# Interconnect_board_v2p0.net
KiCad netlist of a schematic drawn in EAGLE
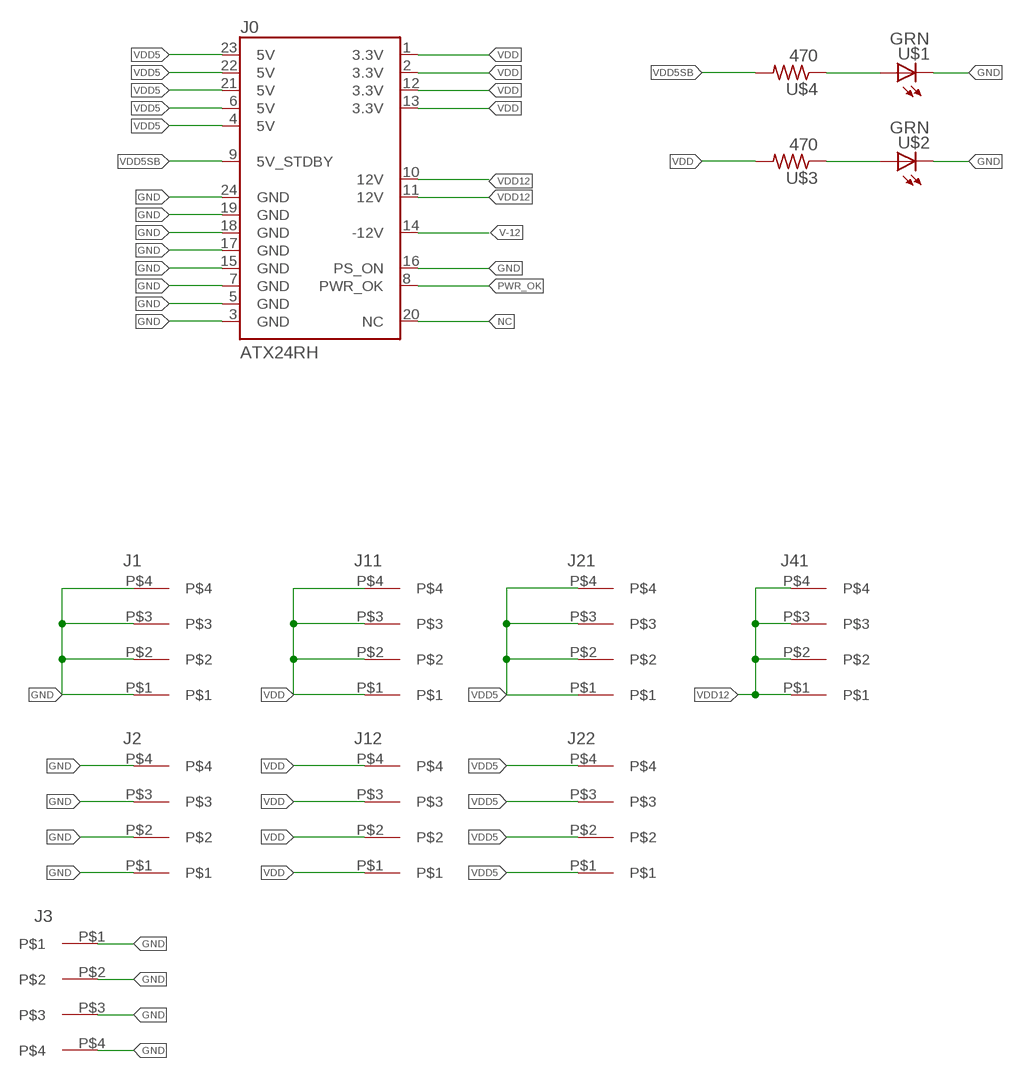
[diagram p0: schematic, sheet 1]

(export (version "E")
  (design (tool "Eeschema 10.0.6"))
  (components
    (comp (ref "J0")
      (value "ATX24RH")
      (footprint "eagle-import:ATX24_RIGHT_ANGLE")
      (libsource (lib "eagle-import") (part "ATX24RH"))
    )
    (comp (ref "J1")
      (value "3.81MM_1_X_4_RT_ANGLE_PLUG_HEADER")
      (footprint "eagle-import:1X4_3.81MM_PITCH")
      (libsource (lib "eagle-import") (part "3.81MM_1_X_4_RT_ANGLE_PLUG_HEADER"))
    )
    (comp (ref "J2")
      (value "3.81MM_1_X_4_RT_ANGLE_PLUG_HEADER")
      (footprint "eagle-import:1X4_3.81MM_PITCH")
      (libsource (lib "eagle-import") (part "3.81MM_1_X_4_RT_ANGLE_PLUG_HEADER"))
    )
    (comp (ref "J3")
      (value "3.81MM_1_X_4_RT_ANGLE_PLUG_HEADER")
      (footprint "eagle-import:1X4_3.81MM_PITCH")
      (libsource (lib "eagle-import") (part "3.81MM_1_X_4_RT_ANGLE_PLUG_HEADER"))
    )
    (comp (ref "J11")
      (value "3.81MM_1_X_4_RT_ANGLE_PLUG_HEADER")
      (footprint "eagle-import:1X4_3.81MM_PITCH")
      (libsource (lib "eagle-import") (part "3.81MM_1_X_4_RT_ANGLE_PLUG_HEADER"))
    )
    (comp (ref "J12")
      (value "3.81MM_1_X_4_RT_ANGLE_PLUG_HEADER")
      (footprint "eagle-import:1X4_3.81MM_PITCH")
      (libsource (lib "eagle-import") (part "3.81MM_1_X_4_RT_ANGLE_PLUG_HEADER"))
    )
    (comp (ref "J21")
      (value "3.81MM_1_X_4_RT_ANGLE_PLUG_HEADER")
      (footprint "eagle-import:1X4_3.81MM_PITCH")
      (libsource (lib "eagle-import") (part "3.81MM_1_X_4_RT_ANGLE_PLUG_HEADER"))
    )
    (comp (ref "J22")
      (value "3.81MM_1_X_4_RT_ANGLE_PLUG_HEADER")
      (footprint "eagle-import:1X4_3.81MM_PITCH")
      (libsource (lib "eagle-import") (part "3.81MM_1_X_4_RT_ANGLE_PLUG_HEADER"))
    )
    (comp (ref "J41")
      (value "3.81MM_1_X_4_RT_ANGLE_PLUG_HEADER")
      (footprint "eagle-import:1X4_3.81MM_PITCH")
      (libsource (lib "eagle-import") (part "3.81MM_1_X_4_RT_ANGLE_PLUG_HEADER"))
    )
    (comp (ref "U$1")
      (value "LED_0805_GREEN")
      (footprint "eagle-import:LED_0805_GREEN")
      (libsource (lib "eagle-import") (part "LED_0805_GREEN"))
    )
    (comp (ref "U$2")
      (value "LED_0805_GREEN")
      (footprint "eagle-import:LED_0805_GREEN")
      (libsource (lib "eagle-import") (part "LED_0805_GREEN"))
    )
    (comp (ref "U$3")
      (value "R_0805_470")
      (footprint "eagle-import:R_0805_470")
      (libsource (lib "eagle-import") (part "R_0805_470"))
    )
    (comp (ref "U$4")
      (value "R_0805_470")
      (footprint "eagle-import:R_0805_470")
      (libsource (lib "eagle-import") (part "R_0805_470"))
    )
  )
  (nets
    (net (code "1") (name "GND") (class "Default")
      (node (ref "J0") (pin "15") (pinfunction "GND_15") (pintype "bidirectional"))
      (node (ref "J0") (pin "16") (pinfunction "PS_ON_16") (pintype "bidirectional"))
      (node (ref "J0") (pin "17") (pinfunction "GND_17") (pintype "bidirectional"))
      (node (ref "J0") (pin "18") (pinfunction "GND_18") (pintype "bidirectional"))
      (node (ref "J0") (pin "19") (pinfunction "GND_19") (pintype "bidirectional"))
      (node (ref "J0") (pin "24") (pinfunction "GND_24") (pintype "bidirectional"))
      (node (ref "J0") (pin "3") (pinfunction "GND_3") (pintype "bidirectional"))
      (node (ref "J0") (pin "5") (pinfunction "GND_5") (pintype "bidirectional"))
      (node (ref "J0") (pin "7") (pinfunction "GND_7") (pintype "bidirectional"))
      (node (ref "J1") (pin "P$1") (pinfunction "P$1_P$1") (pintype "bidirectional"))
      (node (ref "J1") (pin "P$2") (pinfunction "P$2_P$2") (pintype "bidirectional"))
      (node (ref "J1") (pin "P$3") (pinfunction "P$3_P$3") (pintype "bidirectional"))
      (node (ref "J1") (pin "P$4") (pinfunction "P$4_P$4") (pintype "bidirectional"))
      (node (ref "J2") (pin "P$1") (pinfunction "P$1_P$1") (pintype "bidirectional"))
      (node (ref "J2") (pin "P$2") (pinfunction "P$2_P$2") (pintype "bidirectional"))
      (node (ref "J2") (pin "P$3") (pinfunction "P$3_P$3") (pintype "bidirectional"))
      (node (ref "J2") (pin "P$4") (pinfunction "P$4_P$4") (pintype "bidirectional"))
      (node (ref "J3") (pin "P$1") (pinfunction "P$1_P$1") (pintype "bidirectional"))
      (node (ref "J3") (pin "P$2") (pinfunction "P$2_P$2") (pintype "bidirectional"))
      (node (ref "J3") (pin "P$3") (pinfunction "P$3_P$3") (pintype "bidirectional"))
      (node (ref "J3") (pin "P$4") (pinfunction "P$4_P$4") (pintype "bidirectional"))
      (node (ref "U$1") (pin "C") (pinfunction "C_C") (pintype "passive"))
      (node (ref "U$2") (pin "C") (pinfunction "C_C") (pintype "passive"))
    )
    (net (code "2") (name "NC") (class "Default")
      (node (ref "J0") (pin "20") (pinfunction "NC_20") (pintype "bidirectional"))
    )
    (net (code "3") (name "Net-(U$1-PadA)") (class "Default")
      (node (ref "U$1") (pin "A") (pinfunction "A_A") (pintype "passive"))
      (node (ref "U$4") (pin "1") (pinfunction "1_1") (pintype "passive"))
    )
    (net (code "4") (name "Net-(U$2-PadA)") (class "Default")
      (node (ref "U$2") (pin "A") (pinfunction "A_A") (pintype "passive"))
      (node (ref "U$3") (pin "1") (pinfunction "1_1") (pintype "passive"))
    )
    (net (code "5") (name "PWR_OK") (class "Default")
      (node (ref "J0") (pin "8") (pinfunction "PWR_OK_8") (pintype "bidirectional"))
    )
    (net (code "6") (name "V-12") (class "Default")
      (node (ref "J0") (pin "14") (pinfunction "-12V_14") (pintype "bidirectional"))
    )
    (net (code "7") (name "VDD") (class "Default")
      (node (ref "J0") (pin "1") (pinfunction "3.3V_1") (pintype "bidirectional"))
      (node (ref "J0") (pin "12") (pinfunction "3.3V_12") (pintype "bidirectional"))
      (node (ref "J0") (pin "13") (pinfunction "3.3V_13") (pintype "bidirectional"))
      (node (ref "J0") (pin "2") (pinfunction "3.3V_2") (pintype "bidirectional"))
      (node (ref "J11") (pin "P$1") (pinfunction "P$1_P$1") (pintype "bidirectional"))
      (node (ref "J11") (pin "P$2") (pinfunction "P$2_P$2") (pintype "bidirectional"))
      (node (ref "J11") (pin "P$3") (pinfunction "P$3_P$3") (pintype "bidirectional"))
      (node (ref "J11") (pin "P$4") (pinfunction "P$4_P$4") (pintype "bidirectional"))
      (node (ref "J12") (pin "P$1") (pinfunction "P$1_P$1") (pintype "bidirectional"))
      (node (ref "J12") (pin "P$2") (pinfunction "P$2_P$2") (pintype "bidirectional"))
      (node (ref "J12") (pin "P$3") (pinfunction "P$3_P$3") (pintype "bidirectional"))
      (node (ref "J12") (pin "P$4") (pinfunction "P$4_P$4") (pintype "bidirectional"))
      (node (ref "U$3") (pin "2") (pinfunction "2_2") (pintype "passive"))
    )
    (net (code "8") (name "VDD5") (class "Default")
      (node (ref "J0") (pin "21") (pinfunction "5V_21") (pintype "bidirectional"))
      (node (ref "J0") (pin "22") (pinfunction "5V_22") (pintype "bidirectional"))
      (node (ref "J0") (pin "23") (pinfunction "5V_23") (pintype "bidirectional"))
      (node (ref "J0") (pin "4") (pinfunction "5V_4") (pintype "bidirectional"))
      (node (ref "J0") (pin "6") (pinfunction "5V_6") (pintype "bidirectional"))
      (node (ref "J21") (pin "P$1") (pinfunction "P$1_P$1") (pintype "bidirectional"))
      (node (ref "J21") (pin "P$2") (pinfunction "P$2_P$2") (pintype "bidirectional"))
      (node (ref "J21") (pin "P$3") (pinfunction "P$3_P$3") (pintype "bidirectional"))
      (node (ref "J21") (pin "P$4") (pinfunction "P$4_P$4") (pintype "bidirectional"))
      (node (ref "J22") (pin "P$1") (pinfunction "P$1_P$1") (pintype "bidirectional"))
      (node (ref "J22") (pin "P$2") (pinfunction "P$2_P$2") (pintype "bidirectional"))
      (node (ref "J22") (pin "P$3") (pinfunction "P$3_P$3") (pintype "bidirectional"))
      (node (ref "J22") (pin "P$4") (pinfunction "P$4_P$4") (pintype "bidirectional"))
    )
    (net (code "9") (name "VDD5SB") (class "Default")
      (node (ref "J0") (pin "9") (pinfunction "5V_STDBY_9") (pintype "bidirectional"))
      (node (ref "U$4") (pin "2") (pinfunction "2_2") (pintype "passive"))
    )
    (net (code "10") (name "VDD12") (class "Default")
      (node (ref "J0") (pin "10") (pinfunction "12V_10") (pintype "bidirectional"))
      (node (ref "J0") (pin "11") (pinfunction "12V_11") (pintype "bidirectional"))
      (node (ref "J41") (pin "P$1") (pinfunction "P$1_P$1") (pintype "bidirectional"))
      (node (ref "J41") (pin "P$2") (pinfunction "P$2_P$2") (pintype "bidirectional"))
      (node (ref "J41") (pin "P$3") (pinfunction "P$3_P$3") (pintype "bidirectional"))
      (node (ref "J41") (pin "P$4") (pinfunction "P$4_P$4") (pintype "bidirectional"))
    )
  )
)
